# xmegaBreakout.net
KiCad netlist of a schematic drawn in EAGLE
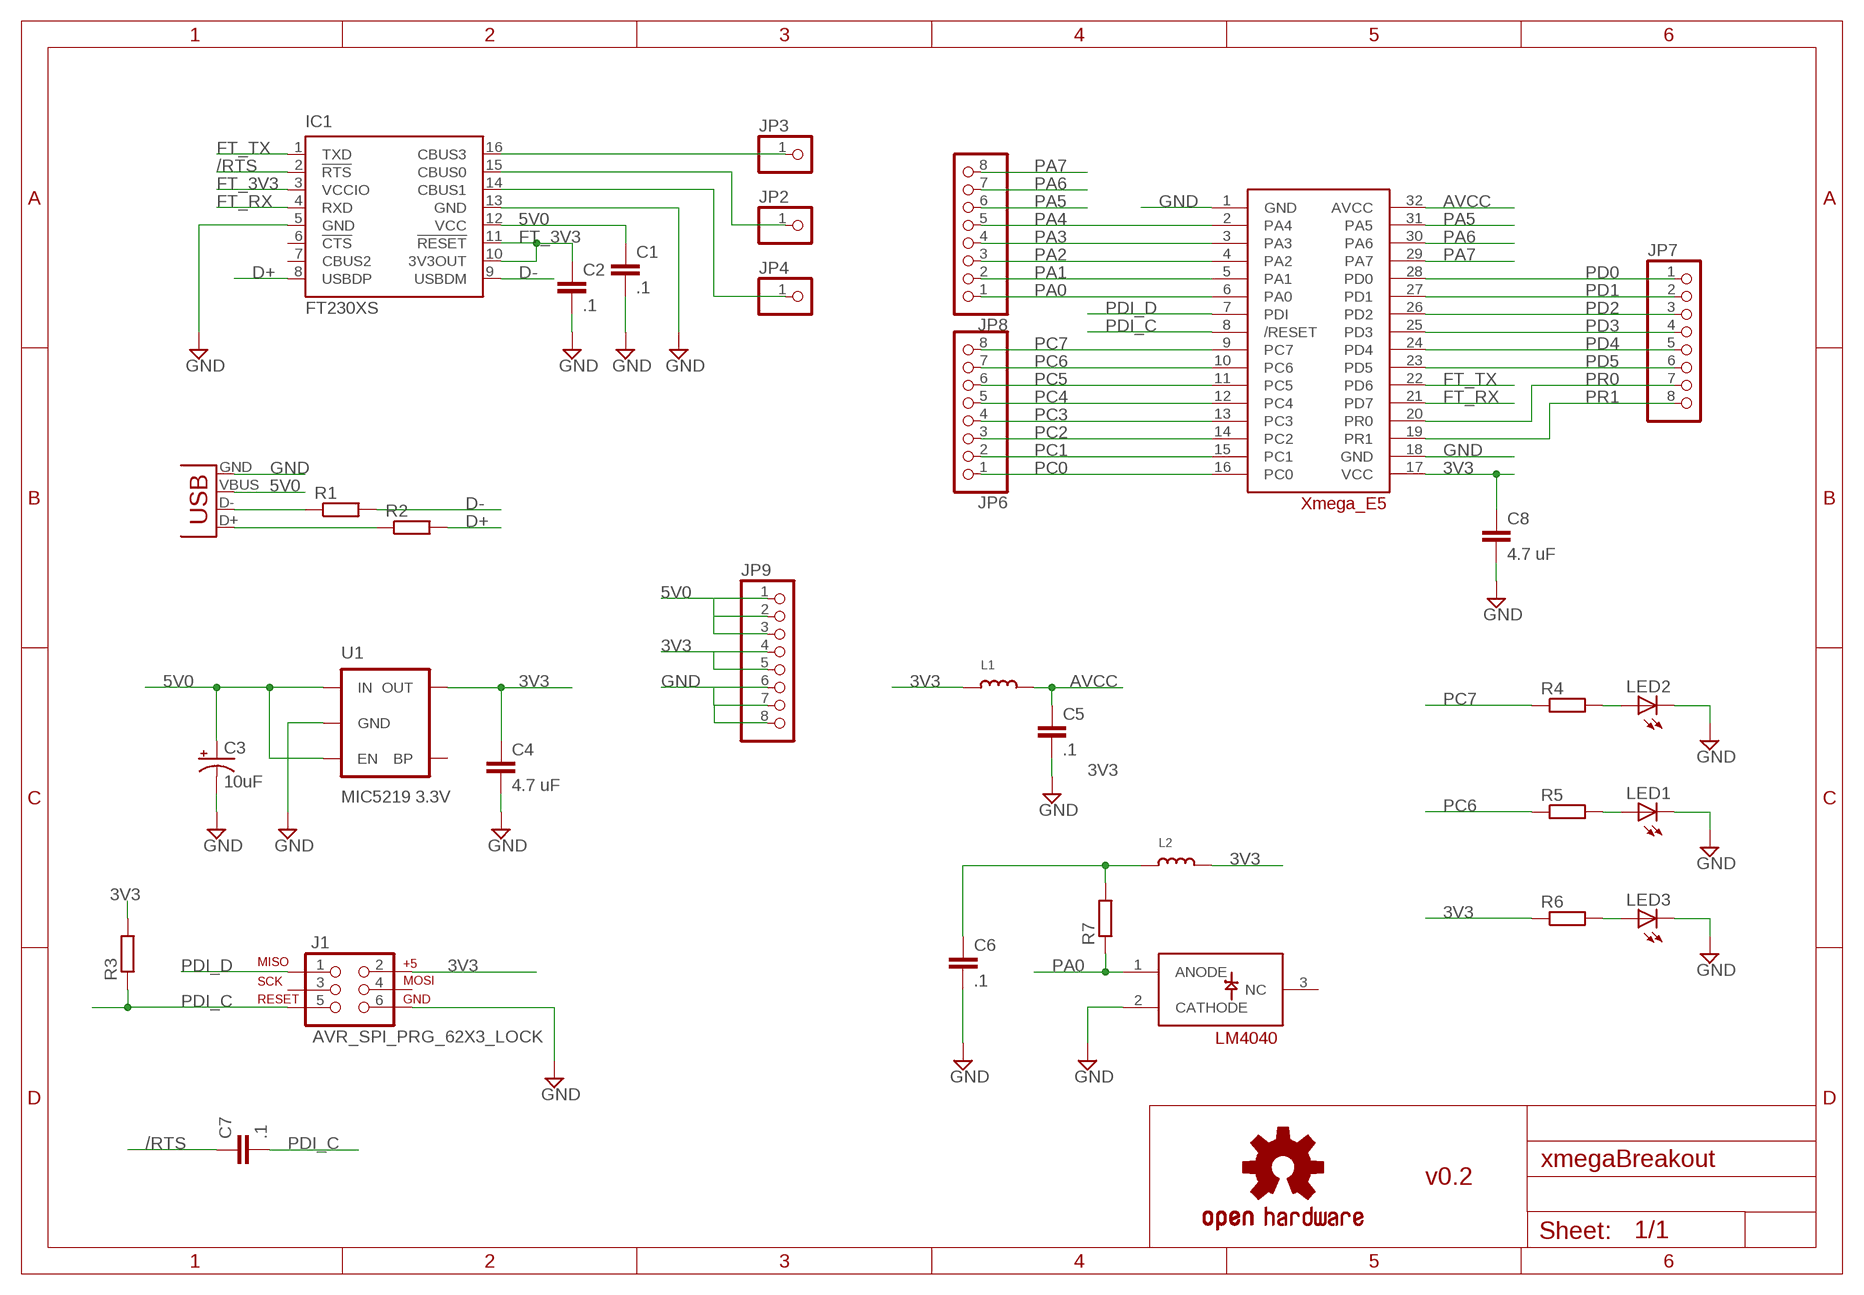
[diagram p0: schematic, sheet 1]

(export (version "E")
  (design (tool "Eeschema 10.0.6"))
  (components
    (comp (ref "C1")
      (value ".1")
      (footprint "eagle-import:C0603")
      (libsource (lib "eagle-import") (part "C-EUC0603"))
    )
    (comp (ref "C2")
      (value ".1")
      (footprint "eagle-import:C0603")
      (libsource (lib "eagle-import") (part "C-EUC0603"))
    )
    (comp (ref "C3")
      (value "10uF")
      (footprint "eagle-import:EIA3216")
      (libsource (lib "eagle-import") (part "10UF-TANT"))
    )
    (comp (ref "C4")
      (value "4.7 uF")
      (footprint "eagle-import:C0603")
      (libsource (lib "eagle-import") (part "C-EUC0603"))
    )
    (comp (ref "C5")
      (value ".1")
      (footprint "eagle-import:C0603")
      (libsource (lib "eagle-import") (part "C-EUC0603"))
    )
    (comp (ref "C6")
      (value ".1")
      (footprint "eagle-import:C0603")
      (libsource (lib "eagle-import") (part "C-EUC0603"))
    )
    (comp (ref "C7")
      (value ".1")
      (footprint "eagle-import:C0603")
      (libsource (lib "eagle-import") (part "C-EUC0603"))
    )
    (comp (ref "C8")
      (value "4.7 uF")
      (footprint "eagle-import:C0603")
      (libsource (lib "eagle-import") (part "C-EUC0603"))
    )
    (comp (ref "IC1")
      (value "FT230XS")
      (footprint "eagle-import:SSOP16")
      (libsource (lib "eagle-import") (part "FT230XS"))
    )
    (comp (ref "J1")
      (value "AVR_SPI_PRG_62X3_LOCK")
      (footprint "eagle-import:2X3_LOCK")
      (libsource (lib "eagle-import") (part "AVR_SPI_PRG_62X3_LOCK"))
    )
    (comp (ref "JP1")
      (value "USBOLD")
      (footprint "eagle-import:USB-MINIB-OLD")
      (libsource (lib "eagle-import") (part "USBOLD"))
    )
    (comp (ref "JP2")
      (value "HEADER-1X1ROUND")
      (footprint "eagle-import:1X01_ROUND")
      (libsource (lib "eagle-import") (part "HEADER-1X1ROUND"))
    )
    (comp (ref "JP3")
      (value "HEADER-1X1ROUND")
      (footprint "eagle-import:1X01_ROUND")
      (libsource (lib "eagle-import") (part "HEADER-1X1ROUND"))
    )
    (comp (ref "JP4")
      (value "HEADER-1X1ROUND")
      (footprint "eagle-import:1X01_ROUND")
      (libsource (lib "eagle-import") (part "HEADER-1X1ROUND"))
    )
    (comp (ref "JP6")
      (value "HEADER-1X8ROUND")
      (footprint "eagle-import:1X08_ROUND")
      (libsource (lib "eagle-import") (part "HEADER-1X8ROUND"))
    )
    (comp (ref "JP7")
      (value "HEADER-1X8ROUND")
      (footprint "eagle-import:1X08_ROUND")
      (libsource (lib "eagle-import") (part "HEADER-1X8ROUND"))
    )
    (comp (ref "JP8")
      (value "HEADER-1X8ROUND")
      (footprint "eagle-import:1X08_ROUND")
      (libsource (lib "eagle-import") (part "HEADER-1X8ROUND"))
    )
    (comp (ref "JP9")
      (value "HEADER-1X8ROUND")
      (footprint "eagle-import:1X08_ROUND")
      (libsource (lib "eagle-import") (part "HEADER-1X8ROUND"))
    )
    (comp (ref "L1")
      (value "INDUCTOR0805")
      (footprint "eagle-import:0805")
      (libsource (lib "eagle-import") (part "INDUCTOR0805"))
    )
    (comp (ref "L2")
      (value "INDUCTOR0805")
      (footprint "eagle-import:0805")
      (libsource (lib "eagle-import") (part "INDUCTOR0805"))
    )
    (comp (ref "LED1")
      (value "LED0603")
      (footprint "eagle-import:LED-0603")
      (libsource (lib "eagle-import") (part "LED0603"))
    )
    (comp (ref "LED2")
      (value "LED0603")
      (footprint "eagle-import:LED-0603")
      (libsource (lib "eagle-import") (part "LED0603"))
    )
    (comp (ref "LED3")
      (value "LED0603")
      (footprint "eagle-import:LED-0603")
      (libsource (lib "eagle-import") (part "LED0603"))
    )
    (comp (ref "LOGO1")
      (value "OSHW-LOGOS")
      (footprint "eagle-import:OSHW-LOGO-S")
      (libsource (lib "eagle-import") (part "OSHW-LOGOS"))
    )
    (comp (ref "R1")
      (value "R-EU_R0603")
      (footprint "eagle-import:R0603")
      (libsource (lib "eagle-import") (part "R-EU_R0603"))
    )
    (comp (ref "R2")
      (value "R-EU_R0603")
      (footprint "eagle-import:R0603")
      (libsource (lib "eagle-import") (part "R-EU_R0603"))
    )
    (comp (ref "R3")
      (value "R-EU_R0603")
      (footprint "eagle-import:R0603")
      (libsource (lib "eagle-import") (part "R-EU_R0603"))
    )
    (comp (ref "R4")
      (value "R-EU_R0603")
      (footprint "eagle-import:R0603")
      (libsource (lib "eagle-import") (part "R-EU_R0603"))
    )
    (comp (ref "R5")
      (value "R-EU_R0603")
      (footprint "eagle-import:R0603")
      (libsource (lib "eagle-import") (part "R-EU_R0603"))
    )
    (comp (ref "R6")
      (value "R-EU_R0603")
      (footprint "eagle-import:R0603")
      (libsource (lib "eagle-import") (part "R-EU_R0603"))
    )
    (comp (ref "R7")
      (value "R-EU_R0603")
      (footprint "eagle-import:R0603")
      (libsource (lib "eagle-import") (part "R-EU_R0603"))
    )
    (comp (ref "U$1")
      (value "IHSAN_XMEGA_E5")
      (footprint "eagle-import:TQFP32-08")
      (libsource (lib "eagle-import") (part "IHSAN_XMEGA_E5"))
    )
    (comp (ref "U$2")
      (value "IHSAN_LM4040")
      (footprint "eagle-import:SOT23-3")
      (libsource (lib "eagle-import") (part "IHSAN_LM4040"))
    )
    (comp (ref "U1")
      (value "MIC5219 3.3V")
      (footprint "eagle-import:SOT23-5")
      (libsource (lib "eagle-import") (part "V_REG_MIC52193.3V"))
    )
  )
  (nets
    (net (code "1") (name "/3V3") (class "Default")
      (node (ref "C4") (pin "1") (pinfunction "1_1") (pintype "passive"))
      (node (ref "C8") (pin "1") (pinfunction "1_1") (pintype "passive"))
      (node (ref "J1") (pin "2") (pinfunction "2_2") (pintype "passive"))
      (node (ref "JP9") (pin "4") (pinfunction "4_4") (pintype "passive"))
      (node (ref "JP9") (pin "5") (pinfunction "5_5") (pintype "passive"))
      (node (ref "L1") (pin "1") (pinfunction "1_1") (pintype "passive"))
      (node (ref "L2") (pin "2") (pinfunction "2_2") (pintype "passive"))
      (node (ref "R3") (pin "2") (pinfunction "2_2") (pintype "passive"))
      (node (ref "R6") (pin "1") (pinfunction "1_1") (pintype "passive"))
      (node (ref "U$1") (pin "17") (pinfunction "VCC_17") (pintype "bidirectional"))
      (node (ref "U1") (pin "5") (pinfunction "OUT_5") (pintype "passive"))
    )
    (net (code "2") (name "/5V0") (class "Default")
      (node (ref "C1") (pin "1") (pinfunction "1_1") (pintype "passive"))
      (node (ref "C3") (pin "A") (pinfunction "+_A") (pintype "passive"))
      (node (ref "IC1") (pin "12") (pinfunction "VCC_12") (pintype "power_in"))
      (node (ref "JP1") (pin "VBUS") (pinfunction "VBUS_VBUS") (pintype "bidirectional"))
      (node (ref "JP9") (pin "1") (pinfunction "1_1") (pintype "passive"))
      (node (ref "JP9") (pin "2") (pinfunction "2_2") (pintype "passive"))
      (node (ref "JP9") (pin "3") (pinfunction "3_3") (pintype "passive"))
      (node (ref "U1") (pin "1") (pinfunction "IN_1") (pintype "input"))
      (node (ref "U1") (pin "3") (pinfunction "EN_3") (pintype "input"))
    )
    (net (code "3") (name "/AVCC") (class "Default")
      (node (ref "C5") (pin "1") (pinfunction "1_1") (pintype "passive"))
      (node (ref "L1") (pin "2") (pinfunction "2_2") (pintype "passive"))
      (node (ref "U$1") (pin "32") (pinfunction "AVCC_32") (pintype "bidirectional"))
    )
    (net (code "4") (name "/D+") (class "Default")
      (node (ref "IC1") (pin "8") (pinfunction "USBDP_8") (pintype "input"))
      (node (ref "R2") (pin "2") (pinfunction "2_2") (pintype "passive"))
    )
    (net (code "5") (name "/D-") (class "Default")
      (node (ref "IC1") (pin "9") (pinfunction "USBDM_9") (pintype "input"))
      (node (ref "R1") (pin "2") (pinfunction "2_2") (pintype "passive"))
    )
    (net (code "6") (name "/FT_3V3") (class "Default")
      (node (ref "C2") (pin "1") (pinfunction "1_1") (pintype "passive"))
      (node (ref "IC1") (pin "10") (pinfunction "3V3OUT_10") (pintype "output"))
      (node (ref "IC1") (pin "11") (pinfunction "~{RESET}_11") (pintype "input"))
      (node (ref "IC1") (pin "3") (pinfunction "VCCIO_3") (pintype "power_in"))
    )
    (net (code "7") (name "/FT_RX") (class "Default")
      (node (ref "IC1") (pin "4") (pinfunction "RXD_4") (pintype "input"))
      (node (ref "U$1") (pin "21") (pinfunction "PD7_21") (pintype "bidirectional"))
    )
    (net (code "8") (name "/FT_TX") (class "Default")
      (node (ref "IC1") (pin "1") (pinfunction "TXD_1") (pintype "output"))
      (node (ref "U$1") (pin "22") (pinfunction "PD6_22") (pintype "bidirectional"))
    )
    (net (code "9") (name "/PA0") (class "Default")
      (node (ref "JP8") (pin "1") (pinfunction "1_1") (pintype "passive"))
      (node (ref "R7") (pin "1") (pinfunction "1_1") (pintype "passive"))
      (node (ref "U$1") (pin "6") (pinfunction "PA0_6") (pintype "bidirectional"))
      (node (ref "U$2") (pin "1") (pinfunction "ANODE_1") (pintype "bidirectional"))
    )
    (net (code "10") (name "/PA1") (class "Default")
      (node (ref "JP8") (pin "2") (pinfunction "2_2") (pintype "passive"))
      (node (ref "U$1") (pin "5") (pinfunction "PA1_5") (pintype "bidirectional"))
    )
    (net (code "11") (name "/PA2") (class "Default")
      (node (ref "JP8") (pin "3") (pinfunction "3_3") (pintype "passive"))
      (node (ref "U$1") (pin "4") (pinfunction "PA2_4") (pintype "bidirectional"))
    )
    (net (code "12") (name "/PA3") (class "Default")
      (node (ref "JP8") (pin "4") (pinfunction "4_4") (pintype "passive"))
      (node (ref "U$1") (pin "3") (pinfunction "PA3_3") (pintype "bidirectional"))
    )
    (net (code "13") (name "/PA4") (class "Default")
      (node (ref "JP8") (pin "5") (pinfunction "5_5") (pintype "passive"))
      (node (ref "U$1") (pin "2") (pinfunction "PA4_2") (pintype "bidirectional"))
    )
    (net (code "14") (name "/PA5") (class "Default")
      (node (ref "JP8") (pin "6") (pinfunction "6_6") (pintype "passive"))
      (node (ref "U$1") (pin "31") (pinfunction "PA5_31") (pintype "bidirectional"))
    )
    (net (code "15") (name "/PA6") (class "Default")
      (node (ref "JP8") (pin "7") (pinfunction "7_7") (pintype "passive"))
      (node (ref "U$1") (pin "30") (pinfunction "PA6_30") (pintype "bidirectional"))
    )
    (net (code "16") (name "/PA7") (class "Default")
      (node (ref "JP8") (pin "8") (pinfunction "8_8") (pintype "passive"))
      (node (ref "U$1") (pin "29") (pinfunction "PA7_29") (pintype "bidirectional"))
    )
    (net (code "17") (name "/PC0") (class "Default")
      (node (ref "JP6") (pin "1") (pinfunction "1_1") (pintype "passive"))
      (node (ref "U$1") (pin "16") (pinfunction "PC0_16") (pintype "bidirectional"))
    )
    (net (code "18") (name "/PC1") (class "Default")
      (node (ref "JP6") (pin "2") (pinfunction "2_2") (pintype "passive"))
      (node (ref "U$1") (pin "15") (pinfunction "PC1_15") (pintype "bidirectional"))
    )
    (net (code "19") (name "/PC2") (class "Default")
      (node (ref "JP6") (pin "3") (pinfunction "3_3") (pintype "passive"))
      (node (ref "U$1") (pin "14") (pinfunction "PC2_14") (pintype "bidirectional"))
    )
    (net (code "20") (name "/PC3") (class "Default")
      (node (ref "JP6") (pin "4") (pinfunction "4_4") (pintype "passive"))
      (node (ref "U$1") (pin "13") (pinfunction "PC3_13") (pintype "bidirectional"))
    )
    (net (code "21") (name "/PC4") (class "Default")
      (node (ref "JP6") (pin "5") (pinfunction "5_5") (pintype "passive"))
      (node (ref "U$1") (pin "12") (pinfunction "PC4_12") (pintype "bidirectional"))
    )
    (net (code "22") (name "/PC5") (class "Default")
      (node (ref "JP6") (pin "6") (pinfunction "6_6") (pintype "passive"))
      (node (ref "U$1") (pin "11") (pinfunction "PC5_11") (pintype "bidirectional"))
    )
    (net (code "23") (name "/PC6") (class "Default")
      (node (ref "JP6") (pin "7") (pinfunction "7_7") (pintype "passive"))
      (node (ref "R5") (pin "1") (pinfunction "1_1") (pintype "passive"))
      (node (ref "U$1") (pin "10") (pinfunction "PC6_10") (pintype "bidirectional"))
    )
    (net (code "24") (name "/PC7") (class "Default")
      (node (ref "JP6") (pin "8") (pinfunction "8_8") (pintype "passive"))
      (node (ref "R4") (pin "1") (pinfunction "1_1") (pintype "passive"))
      (node (ref "U$1") (pin "9") (pinfunction "PC7_9") (pintype "bidirectional"))
    )
    (net (code "25") (name "/PD0") (class "Default")
      (node (ref "JP7") (pin "1") (pinfunction "1_1") (pintype "passive"))
      (node (ref "U$1") (pin "28") (pinfunction "PD0_28") (pintype "bidirectional"))
    )
    (net (code "26") (name "/PD1") (class "Default")
      (node (ref "JP7") (pin "2") (pinfunction "2_2") (pintype "passive"))
      (node (ref "U$1") (pin "27") (pinfunction "PD1_27") (pintype "bidirectional"))
    )
    (net (code "27") (name "/PD2") (class "Default")
      (node (ref "JP7") (pin "3") (pinfunction "3_3") (pintype "passive"))
      (node (ref "U$1") (pin "26") (pinfunction "PD2_26") (pintype "bidirectional"))
    )
    (net (code "28") (name "/PD3") (class "Default")
      (node (ref "JP7") (pin "4") (pinfunction "4_4") (pintype "passive"))
      (node (ref "U$1") (pin "25") (pinfunction "PD3_25") (pintype "bidirectional"))
    )
    (net (code "29") (name "/PD4") (class "Default")
      (node (ref "JP7") (pin "5") (pinfunction "5_5") (pintype "passive"))
      (node (ref "U$1") (pin "24") (pinfunction "PD4_24") (pintype "bidirectional"))
    )
    (net (code "30") (name "/PD5") (class "Default")
      (node (ref "JP7") (pin "6") (pinfunction "6_6") (pintype "passive"))
      (node (ref "U$1") (pin "23") (pinfunction "PD5_23") (pintype "bidirectional"))
    )
    (net (code "31") (name "/PDI_C") (class "Default")
      (node (ref "C7") (pin "2") (pinfunction "2_2") (pintype "passive"))
      (node (ref "J1") (pin "5") (pinfunction "5_5") (pintype "passive"))
      (node (ref "R3") (pin "1") (pinfunction "1_1") (pintype "passive"))
      (node (ref "U$1") (pin "8") (pinfunction "/RESET_8") (pintype "bidirectional"))
    )
    (net (code "32") (name "/PDI_D") (class "Default")
      (node (ref "J1") (pin "1") (pinfunction "1_1") (pintype "passive"))
      (node (ref "U$1") (pin "7") (pinfunction "PDI_7") (pintype "bidirectional"))
    )
    (net (code "33") (name "/PR0") (class "Default")
      (node (ref "JP7") (pin "7") (pinfunction "7_7") (pintype "passive"))
      (node (ref "U$1") (pin "20") (pinfunction "PR0_20") (pintype "bidirectional"))
    )
    (net (code "34") (name "/PR1") (class "Default")
      (node (ref "JP7") (pin "8") (pinfunction "8_8") (pintype "passive"))
      (node (ref "U$1") (pin "19") (pinfunction "PR1_19") (pintype "bidirectional"))
    )
    (net (code "35") (name "/{slash}RTS") (class "Default")
      (node (ref "C7") (pin "1") (pinfunction "1_1") (pintype "passive"))
      (node (ref "IC1") (pin "2") (pinfunction "~{RTS}_2") (pintype "output"))
    )
    (net (code "36") (name "GND") (class "Default")
      (node (ref "C1") (pin "2") (pinfunction "2_2") (pintype "passive"))
      (node (ref "C2") (pin "2") (pinfunction "2_2") (pintype "passive"))
      (node (ref "C3") (pin "C") (pinfunction "-_C") (pintype "passive"))
      (node (ref "C4") (pin "2") (pinfunction "2_2") (pintype "passive"))
      (node (ref "C5") (pin "2") (pinfunction "2_2") (pintype "passive"))
      (node (ref "C6") (pin "2") (pinfunction "2_2") (pintype "passive"))
      (node (ref "C8") (pin "2") (pinfunction "2_2") (pintype "passive"))
      (node (ref "IC1") (pin "13") (pinfunction "GND_13") (pintype "power_in"))
      (node (ref "IC1") (pin "5") (pinfunction "GND_5") (pintype "power_in"))
      (node (ref "J1") (pin "6") (pinfunction "6_6") (pintype "passive"))
      (node (ref "JP1") (pin "GND") (pinfunction "GND_GND") (pintype "bidirectional"))
      (node (ref "JP9") (pin "6") (pinfunction "6_6") (pintype "passive"))
      (node (ref "JP9") (pin "7") (pinfunction "7_7") (pintype "passive"))
      (node (ref "JP9") (pin "8") (pinfunction "8_8") (pintype "passive"))
      (node (ref "LED1") (pin "C") (pinfunction "C_C") (pintype "passive"))
      (node (ref "LED2") (pin "C") (pinfunction "C_C") (pintype "passive"))
      (node (ref "LED3") (pin "C") (pinfunction "C_C") (pintype "passive"))
      (node (ref "U$1") (pin "1") (pinfunction "GND_1") (pintype "bidirectional"))
      (node (ref "U$1") (pin "18") (pinfunction "GND_18") (pintype "bidirectional"))
      (node (ref "U$2") (pin "2") (pinfunction "CATHODE_2") (pintype "bidirectional"))
      (node (ref "U1") (pin "2") (pinfunction "GND_2") (pintype "input"))
    )
    (net (code "37") (name "Net-(C6-Pad1)") (class "Default")
      (node (ref "C6") (pin "1") (pinfunction "1_1") (pintype "passive"))
      (node (ref "L2") (pin "1") (pinfunction "1_1") (pintype "passive"))
      (node (ref "R7") (pin "2") (pinfunction "2_2") (pintype "passive"))
    )
    (net (code "38") (name "Net-(IC1-CBUS0)") (class "Default")
      (node (ref "IC1") (pin "15") (pinfunction "CBUS0_15") (pintype "bidirectional"))
      (node (ref "JP2") (pin "1") (pinfunction "1_1") (pintype "passive"))
    )
    (net (code "39") (name "Net-(IC1-CBUS1)") (class "Default")
      (node (ref "IC1") (pin "14") (pinfunction "CBUS1_14") (pintype "bidirectional"))
      (node (ref "JP4") (pin "1") (pinfunction "1_1") (pintype "passive"))
    )
    (net (code "40") (name "Net-(IC1-CBUS3)") (class "Default")
      (node (ref "IC1") (pin "16") (pinfunction "CBUS3_16") (pintype "bidirectional"))
      (node (ref "JP3") (pin "1") (pinfunction "1_1") (pintype "passive"))
    )
    (net (code "41") (name "Net-(JP1-PadD+)") (class "Default")
      (node (ref "JP1") (pin "D+") (pinfunction "D+_D+") (pintype "bidirectional"))
      (node (ref "R2") (pin "1") (pinfunction "1_1") (pintype "passive"))
    )
    (net (code "42") (name "Net-(JP1-PadD-)") (class "Default")
      (node (ref "JP1") (pin "D-") (pinfunction "D-_D-") (pintype "bidirectional"))
      (node (ref "R1") (pin "1") (pinfunction "1_1") (pintype "passive"))
    )
    (net (code "43") (name "Net-(LED1-PadA)") (class "Default")
      (node (ref "LED1") (pin "A") (pinfunction "A_A") (pintype "passive"))
      (node (ref "R5") (pin "2") (pinfunction "2_2") (pintype "passive"))
    )
    (net (code "44") (name "Net-(LED2-PadA)") (class "Default")
      (node (ref "LED2") (pin "A") (pinfunction "A_A") (pintype "passive"))
      (node (ref "R4") (pin "2") (pinfunction "2_2") (pintype "passive"))
    )
    (net (code "45") (name "Net-(LED3-PadA)") (class "Default")
      (node (ref "LED3") (pin "A") (pinfunction "A_A") (pintype "passive"))
      (node (ref "R6") (pin "2") (pinfunction "2_2") (pintype "passive"))
    )
    (net (code "46") (name "unconnected-(IC1-CBUS2-Pad7)") (class "Default")
      (node (ref "IC1") (pin "7") (pinfunction "CBUS2_7") (pintype "bidirectional"))
    )
    (net (code "47") (name "unconnected-(IC1-~{CTS}-Pad6)") (class "Default")
      (node (ref "IC1") (pin "6") (pinfunction "~{CTS}_6") (pintype "input"))
    )
    (net (code "48") (name "unconnected-(J1-Pad3)") (class "Default")
      (node (ref "J1") (pin "3") (pinfunction "3_3") (pintype "passive"))
    )
    (net (code "49") (name "unconnected-(J1-Pad4)") (class "Default")
      (node (ref "J1") (pin "4") (pinfunction "4_4") (pintype "passive"))
    )
    (net (code "50") (name "unconnected-(U$2-NC-Pad3)") (class "Default")
      (node (ref "U$2") (pin "3") (pinfunction "NC_3") (pintype "bidirectional"))
    )
    (net (code "51") (name "unconnected-(U1-BP-Pad4)") (class "Default")
      (node (ref "U1") (pin "4") (pinfunction "BP_4") (pintype "input"))
    )
  )
)
